# ENC_CON.net
KiCad netlist of a schematic drawn in EAGLE
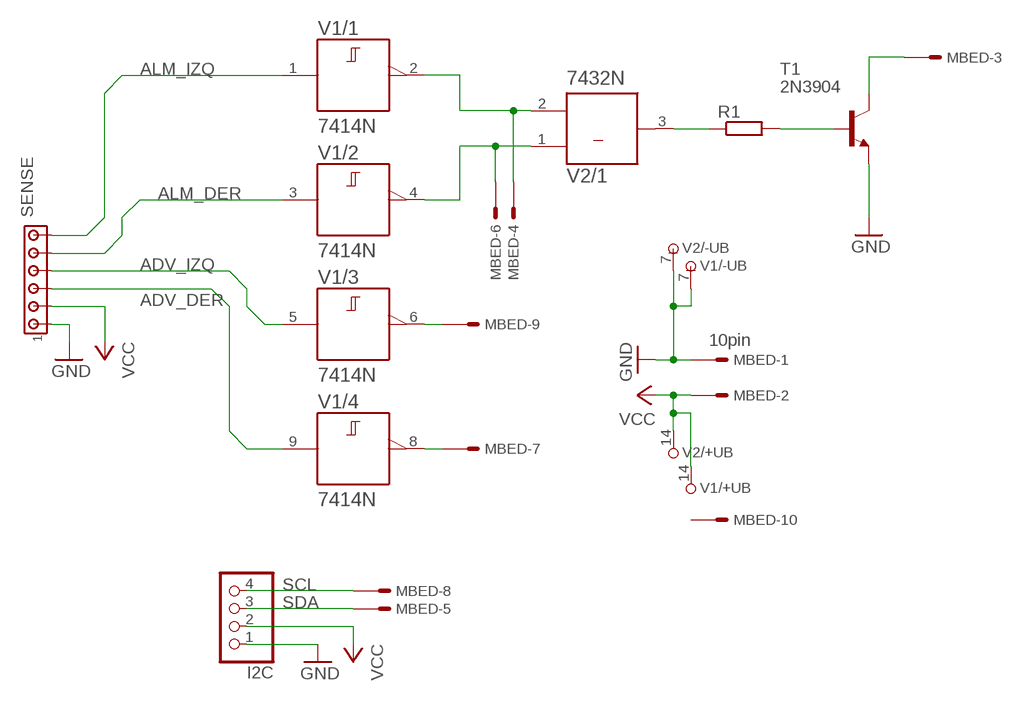
[diagram p0: schematic, sheet 1]

(export (version "E")
  (design (tool "Eeschema 10.0.6"))
  (components
    (comp (ref "I2C")
      (value "PINHD-1X4/90")
      (footprint "eagle-import:1X04_90")
      (libsource (lib "eagle-import") (part "PINHD-1X4/90"))
    )
    (comp (ref "MBED")
      (value "10pin")
      (footprint "eagle-import:057-010-1")
      (libsource (lib "eagle-import") (part "057-010-1"))
    )
    (comp (ref "R1")
      (value "R-EU_0207/10")
      (footprint "eagle-import:0207_10")
      (libsource (lib "eagle-import") (part "R-EU_0207/10"))
    )
    (comp (ref "SENSE")
      (value "MTA06-100")
      (footprint "eagle-import:10X06MTA")
      (libsource (lib "eagle-import") (part "MTA06-100"))
    )
    (comp (ref "T1")
      (value "2N3904")
      (footprint "eagle-import:TO92")
      (libsource (lib "eagle-import") (part "2N3904"))
    )
    (comp (ref "V1")
      (value "7414N")
      (footprint "eagle-import:DIL14")
      (libsource (lib "eagle-import") (part "7414N"))
    )
    (comp (ref "V2")
      (value "7432N")
      (footprint "eagle-import:DIL14")
      (libsource (lib "eagle-import") (part "7432N"))
    )
  )
  (nets
    (net (code "1") (name "/ADV_DER") (class "Default")
      (node (ref "SENSE") (pin "4") (pinfunction "3_4") (pintype "passive"))
      (node (ref "V1") (pin "9") (pinfunction "A_9") (pintype "input"))
    )
    (net (code "2") (name "/ADV_IZQ") (class "Default")
      (node (ref "SENSE") (pin "3") (pinfunction "4_3") (pintype "passive"))
      (node (ref "V1") (pin "5") (pinfunction "A_5") (pintype "input"))
    )
    (net (code "3") (name "/ALM_DER") (class "Default")
      (node (ref "SENSE") (pin "2") (pinfunction "5_2") (pintype "passive"))
      (node (ref "V1") (pin "3") (pinfunction "A_3") (pintype "input"))
    )
    (net (code "4") (name "/ALM_IZQ") (class "Default")
      (node (ref "SENSE") (pin "1") (pinfunction "6_1") (pintype "passive"))
      (node (ref "V1") (pin "1") (pinfunction "A_1") (pintype "input"))
    )
    (net (code "5") (name "/SCL") (class "Default")
      (node (ref "I2C") (pin "4") (pinfunction "4_4") (pintype "passive"))
      (node (ref "MBED") (pin "8") (pinfunction "S_8") (pintype "passive"))
    )
    (net (code "6") (name "/SDA") (class "Default")
      (node (ref "I2C") (pin "3") (pinfunction "3_3") (pintype "passive"))
      (node (ref "MBED") (pin "5") (pinfunction "S_5") (pintype "passive"))
    )
    (net (code "7") (name "GND") (class "Default")
      (node (ref "I2C") (pin "1") (pinfunction "1_1") (pintype "passive"))
      (node (ref "MBED") (pin "1") (pinfunction "S_1") (pintype "passive"))
      (node (ref "SENSE") (pin "6") (pinfunction "1_6") (pintype "passive"))
      (node (ref "T1") (pin "3") (pinfunction "E_3") (pintype "passive"))
      (node (ref "V1") (pin "7") (pinfunction "-UB_7") (pintype "power_in"))
      (node (ref "V2") (pin "7") (pinfunction "-UB_7") (pintype "power_in"))
    )
    (net (code "8") (name "Net-(MBEDD-S)") (class "Default")
      (node (ref "MBED") (pin "3") (pinfunction "S_3") (pintype "passive"))
      (node (ref "T1") (pin "1") (pinfunction "C_1") (pintype "passive"))
    )
    (net (code "9") (name "Net-(MBEDE-S)") (class "Default")
      (node (ref "MBED") (pin "4") (pinfunction "S_4") (pintype "passive"))
      (node (ref "V1") (pin "2") (pinfunction "Y_2") (pintype "output"))
      (node (ref "V2") (pin "2") (pinfunction "B_2") (pintype "input"))
    )
    (net (code "10") (name "Net-(MBEDG-S)") (class "Default")
      (node (ref "MBED") (pin "6") (pinfunction "S_6") (pintype "passive"))
      (node (ref "V1") (pin "4") (pinfunction "Y_4") (pintype "output"))
      (node (ref "V2") (pin "1") (pinfunction "A_1") (pintype "input"))
    )
    (net (code "11") (name "Net-(MBEDH-S)") (class "Default")
      (node (ref "MBED") (pin "7") (pinfunction "S_7") (pintype "passive"))
      (node (ref "V1") (pin "8") (pinfunction "Y_8") (pintype "output"))
    )
    (net (code "12") (name "Net-(MBEDJ-S)") (class "Default")
      (node (ref "MBED") (pin "9") (pinfunction "S_9") (pintype "passive"))
      (node (ref "V1") (pin "6") (pinfunction "Y_6") (pintype "output"))
    )
    (net (code "13") (name "Net-(T1-B)") (class "Default")
      (node (ref "R1") (pin "2") (pinfunction "2_2") (pintype "passive"))
      (node (ref "T1") (pin "2") (pinfunction "B_2") (pintype "passive"))
    )
    (net (code "14") (name "Net-(V2C-Y)") (class "Default")
      (node (ref "R1") (pin "1") (pinfunction "1_1") (pintype "passive"))
      (node (ref "V2") (pin "3") (pinfunction "Y_3") (pintype "output"))
    )
    (net (code "15") (name "VCC") (class "Default")
      (node (ref "I2C") (pin "2") (pinfunction "2_2") (pintype "passive"))
      (node (ref "MBED") (pin "2") (pinfunction "S_2") (pintype "passive"))
      (node (ref "SENSE") (pin "5") (pinfunction "2_5") (pintype "passive"))
      (node (ref "V1") (pin "14") (pinfunction "+UB_14") (pintype "power_in"))
      (node (ref "V2") (pin "14") (pinfunction "+UB_14") (pintype "power_in"))
    )
    (net (code "16") (name "unconnected-(MBEDB-S-Pad10)") (class "Default")
      (node (ref "MBED") (pin "10") (pinfunction "S_10") (pintype "passive"))
    )
  )
)
